# AutoFeatherDoubler.net
KiCad netlist of a schematic drawn in EAGLE
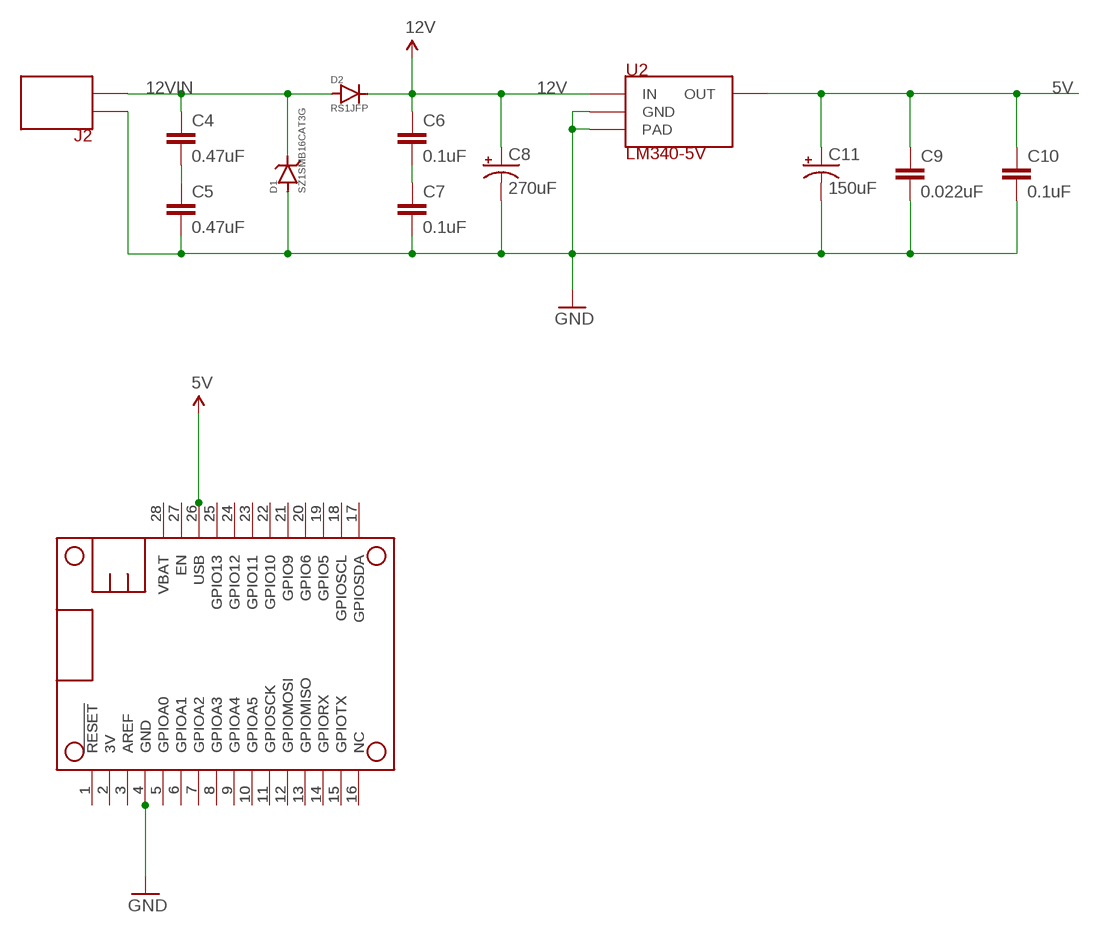
[diagram p0: schematic, sheet 1]

(export (version "E")
  (design (tool "Eeschema 10.0.6"))
  (components
    (comp (ref "C4")
      (value "0.47uF")
      (footprint "eagle-import:0805")
      (libsource (lib "eagle-import") (part "CAP-0.47UF-0805"))
    )
    (comp (ref "C5")
      (value "0.47uF")
      (footprint "eagle-import:0805")
      (libsource (lib "eagle-import") (part "CAP-0.47UF-0805"))
    )
    (comp (ref "C6")
      (value "0.1uF")
      (footprint "eagle-import:0603-CAP")
      (libsource (lib "eagle-import") (part "CAP-0.1UF-0603"))
    )
    (comp (ref "C7")
      (value "0.1uF")
      (footprint "eagle-import:0603-CAP")
      (libsource (lib "eagle-import") (part "CAP-0.1UF-0603"))
    )
    (comp (ref "C8")
      (value "270uF")
      (footprint "eagle-import:CAP-270UF-25V-RADIAL-PTH")
      (libsource (lib "eagle-import") (part "CAP-270UF-25V-RADIAL-PTH"))
    )
    (comp (ref "C9")
      (value "0.022uF")
      (footprint "eagle-import:0603-CAP")
      (libsource (lib "eagle-import") (part "CAP-0.022UF-0603"))
    )
    (comp (ref "C10")
      (value "0.1uF")
      (footprint "eagle-import:0603-CAP")
      (libsource (lib "eagle-import") (part "CAP-0.1UF-0603"))
    )
    (comp (ref "C11")
      (value "150uF")
      (footprint "eagle-import:CAP-150UF-25V-RADIAL-PTH")
      (libsource (lib "eagle-import") (part "CAP-150UF-25V-RADIAL-PTH"))
    )
    (comp (ref "D1")
      (value "SZ1SMB16CAT3G")
      (footprint "eagle-import:SZ1SMB")
      (libsource (lib "eagle-import") (part "DIODE-TVS-SZ1SMB"))
    )
    (comp (ref "D2")
      (value "RS1JFP")
      (footprint "eagle-import:SOD-123HE-ON")
      (libsource (lib "eagle-import") (part "DIODE-RS1JFP"))
    )
    (comp (ref "J2")
      (value "TERMBLOCK-2X3.5MM")
      (footprint "eagle-import:TERMBLOCK-2X3.5MM")
      (libsource (lib "eagle-import") (part "TERMBLOCK-2X3.5MM"))
    )
    (comp (ref "MS1")
      (value "FEATHERWING_NODIM")
      (footprint "eagle-import:FEATHERWING_DIM")
      (libsource (lib "eagle-import") (part "FEATHERWING_NODIM"))
    )
    (comp (ref "MS2")
      (value "FEATHERWING_NODIM")
      (footprint "eagle-import:FEATHERWING_DIM")
      (libsource (lib "eagle-import") (part "FEATHERWING_NODIM"))
    )
    (comp (ref "U2")
      (value "LM340-5V")
      (footprint "eagle-import:TO-263-3-TI")
      (libsource (lib "eagle-import") (part "LM340"))
    )
  )
  (nets
    (net (code "1") (name "/12VIN") (class "Default")
      (node (ref "C4") (pin "1") (pinfunction "1_1") (pintype "passive"))
      (node (ref "D1") (pin "C") (pinfunction "CATHODE_C") (pintype "bidirectional"))
      (node (ref "D2") (pin "2") (pinfunction "ANODE_2") (pintype "bidirectional"))
      (node (ref "J2") (pin "2") (pinfunction "2_2") (pintype "passive"))
    )
    (net (code "2") (name "5V") (class "Default")
      (node (ref "C10") (pin "1") (pinfunction "1_1") (pintype "passive"))
      (node (ref "C11") (pin "+") (pinfunction "+_+") (pintype "passive"))
      (node (ref "C9") (pin "1") (pinfunction "1_1") (pintype "passive"))
      (node (ref "MS1") (pin "26") (pinfunction "USB_26") (pintype "power_in"))
      (node (ref "MS2") (pin "26") (pinfunction "USB_26") (pintype "power_in"))
      (node (ref "U2") (pin "3") (pinfunction "OUT_3") (pintype "power_in"))
    )
    (net (code "3") (name "12V") (class "Default")
      (node (ref "C6") (pin "1") (pinfunction "1_1") (pintype "passive"))
      (node (ref "C8") (pin "+") (pinfunction "+_+") (pintype "passive"))
      (node (ref "D2") (pin "1") (pinfunction "CATHODE_1") (pintype "bidirectional"))
      (node (ref "U2") (pin "1") (pinfunction "IN_1") (pintype "power_in"))
    )
    (net (code "4") (name "GND") (class "Default")
      (node (ref "C10") (pin "2") (pinfunction "2_2") (pintype "passive"))
      (node (ref "C11") (pin "-") (pinfunction "-_-") (pintype "passive"))
      (node (ref "C5") (pin "2") (pinfunction "2_2") (pintype "passive"))
      (node (ref "C7") (pin "2") (pinfunction "2_2") (pintype "passive"))
      (node (ref "C8") (pin "-") (pinfunction "-_-") (pintype "passive"))
      (node (ref "C9") (pin "2") (pinfunction "2_2") (pintype "passive"))
      (node (ref "D1") (pin "A") (pinfunction "ANODE_A") (pintype "bidirectional"))
      (node (ref "J2") (pin "1") (pinfunction "1_1") (pintype "passive"))
      (node (ref "MS1") (pin "4") (pinfunction "GND_4") (pintype "power_in"))
      (node (ref "MS2") (pin "4") (pinfunction "GND_4") (pintype "power_in"))
      (node (ref "U2") (pin "2") (pinfunction "GND_2") (pintype "power_in"))
      (node (ref "U2") (pin "PAD") (pinfunction "PAD_PAD") (pintype "power_in"))
    )
    (net (code "5") (name "Net-(C4-Pad2)") (class "Default")
      (node (ref "C4") (pin "2") (pinfunction "2_2") (pintype "passive"))
      (node (ref "C5") (pin "1") (pinfunction "1_1") (pintype "passive"))
    )
    (net (code "6") (name "Net-(C6-Pad2)") (class "Default")
      (node (ref "C6") (pin "2") (pinfunction "2_2") (pintype "passive"))
      (node (ref "C7") (pin "1") (pinfunction "1_1") (pintype "passive"))
    )
    (net (code "7") (name "Net-(MS1-3V)") (class "Default")
      (node (ref "MS1") (pin "2") (pinfunction "3V_2") (pintype "power_in"))
      (node (ref "MS2") (pin "2") (pinfunction "3V_2") (pintype "power_in"))
    )
    (net (code "8") (name "Net-(MS1-AREF)") (class "Default")
      (node (ref "MS1") (pin "3") (pinfunction "AREF_3") (pintype "passive"))
      (node (ref "MS2") (pin "3") (pinfunction "AREF_3") (pintype "passive"))
    )
    (net (code "9") (name "Net-(MS1-EN)") (class "Default")
      (node (ref "MS1") (pin "27") (pinfunction "EN_27") (pintype "passive"))
      (node (ref "MS2") (pin "27") (pinfunction "EN_27") (pintype "passive"))
    )
    (net (code "10") (name "Net-(MS1-GPIO5)") (class "Default")
      (node (ref "MS1") (pin "19") (pinfunction "GPIO5_19") (pintype "bidirectional"))
      (node (ref "MS2") (pin "19") (pinfunction "GPIO5_19") (pintype "bidirectional"))
    )
    (net (code "11") (name "Net-(MS1-GPIO6)") (class "Default")
      (node (ref "MS1") (pin "20") (pinfunction "GPIO6_20") (pintype "bidirectional"))
      (node (ref "MS2") (pin "20") (pinfunction "GPIO6_20") (pintype "bidirectional"))
    )
    (net (code "12") (name "Net-(MS1-GPIO9)") (class "Default")
      (node (ref "MS1") (pin "21") (pinfunction "GPIO9_21") (pintype "bidirectional"))
      (node (ref "MS2") (pin "21") (pinfunction "GPIO9_21") (pintype "bidirectional"))
    )
    (net (code "13") (name "Net-(MS1-GPIO10)") (class "Default")
      (node (ref "MS1") (pin "22") (pinfunction "GPIO10_22") (pintype "bidirectional"))
      (node (ref "MS2") (pin "22") (pinfunction "GPIO10_22") (pintype "bidirectional"))
    )
    (net (code "14") (name "Net-(MS1-GPIO11)") (class "Default")
      (node (ref "MS1") (pin "23") (pinfunction "GPIO11_23") (pintype "bidirectional"))
      (node (ref "MS2") (pin "23") (pinfunction "GPIO11_23") (pintype "bidirectional"))
    )
    (net (code "15") (name "Net-(MS1-GPIO12)") (class "Default")
      (node (ref "MS1") (pin "24") (pinfunction "GPIO12_24") (pintype "bidirectional"))
      (node (ref "MS2") (pin "24") (pinfunction "GPIO12_24") (pintype "bidirectional"))
    )
    (net (code "16") (name "Net-(MS1-GPIO13)") (class "Default")
      (node (ref "MS1") (pin "25") (pinfunction "GPIO13_25") (pintype "bidirectional"))
      (node (ref "MS2") (pin "25") (pinfunction "GPIO13_25") (pintype "bidirectional"))
    )
    (net (code "17") (name "Net-(MS1-GPIOA0)") (class "Default")
      (node (ref "MS1") (pin "5") (pinfunction "GPIOA0_5") (pintype "bidirectional"))
      (node (ref "MS2") (pin "5") (pinfunction "GPIOA0_5") (pintype "bidirectional"))
    )
    (net (code "18") (name "Net-(MS1-GPIOA1)") (class "Default")
      (node (ref "MS1") (pin "6") (pinfunction "GPIOA1_6") (pintype "bidirectional"))
      (node (ref "MS2") (pin "6") (pinfunction "GPIOA1_6") (pintype "bidirectional"))
    )
    (net (code "19") (name "Net-(MS1-GPIOA2)") (class "Default")
      (node (ref "MS1") (pin "7") (pinfunction "GPIOA2_7") (pintype "bidirectional"))
      (node (ref "MS2") (pin "7") (pinfunction "GPIOA2_7") (pintype "bidirectional"))
    )
    (net (code "20") (name "Net-(MS1-GPIOA3)") (class "Default")
      (node (ref "MS1") (pin "8") (pinfunction "GPIOA3_8") (pintype "bidirectional"))
      (node (ref "MS2") (pin "8") (pinfunction "GPIOA3_8") (pintype "bidirectional"))
    )
    (net (code "21") (name "Net-(MS1-GPIOA4)") (class "Default")
      (node (ref "MS1") (pin "9") (pinfunction "GPIOA4_9") (pintype "bidirectional"))
      (node (ref "MS2") (pin "9") (pinfunction "GPIOA4_9") (pintype "bidirectional"))
    )
    (net (code "22") (name "Net-(MS1-GPIOA5)") (class "Default")
      (node (ref "MS1") (pin "10") (pinfunction "GPIOA5_10") (pintype "bidirectional"))
      (node (ref "MS2") (pin "10") (pinfunction "GPIOA5_10") (pintype "bidirectional"))
    )
    (net (code "23") (name "Net-(MS1-GPIOMISO)") (class "Default")
      (node (ref "MS1") (pin "13") (pinfunction "GPIOMISO_13") (pintype "bidirectional"))
      (node (ref "MS2") (pin "13") (pinfunction "GPIOMISO_13") (pintype "bidirectional"))
    )
    (net (code "24") (name "Net-(MS1-GPIOMOSI)") (class "Default")
      (node (ref "MS1") (pin "12") (pinfunction "GPIOMOSI_12") (pintype "bidirectional"))
      (node (ref "MS2") (pin "12") (pinfunction "GPIOMOSI_12") (pintype "bidirectional"))
    )
    (net (code "25") (name "Net-(MS1-GPIORX)") (class "Default")
      (node (ref "MS1") (pin "14") (pinfunction "GPIORX_14") (pintype "bidirectional"))
      (node (ref "MS2") (pin "14") (pinfunction "GPIORX_14") (pintype "bidirectional"))
    )
    (net (code "26") (name "Net-(MS1-GPIOSCK)") (class "Default")
      (node (ref "MS1") (pin "11") (pinfunction "GPIOSCK_11") (pintype "bidirectional"))
      (node (ref "MS2") (pin "11") (pinfunction "GPIOSCK_11") (pintype "bidirectional"))
    )
    (net (code "27") (name "Net-(MS1-GPIOSCL)") (class "Default")
      (node (ref "MS1") (pin "18") (pinfunction "GPIOSCL_18") (pintype "bidirectional"))
      (node (ref "MS2") (pin "18") (pinfunction "GPIOSCL_18") (pintype "bidirectional"))
    )
    (net (code "28") (name "Net-(MS1-GPIOSDA)") (class "Default")
      (node (ref "MS1") (pin "17") (pinfunction "GPIOSDA_17") (pintype "bidirectional"))
      (node (ref "MS2") (pin "17") (pinfunction "GPIOSDA_17") (pintype "bidirectional"))
    )
    (net (code "29") (name "Net-(MS1-GPIOTX)") (class "Default")
      (node (ref "MS1") (pin "15") (pinfunction "GPIOTX_15") (pintype "bidirectional"))
      (node (ref "MS2") (pin "15") (pinfunction "GPIOTX_15") (pintype "bidirectional"))
    )
    (net (code "30") (name "Net-(MS1-NC)") (class "Default")
      (node (ref "MS1") (pin "16") (pinfunction "NC_16") (pintype "passive"))
      (node (ref "MS2") (pin "16") (pinfunction "NC_16") (pintype "passive"))
    )
    (net (code "31") (name "Net-(MS1-VBAT)") (class "Default")
      (node (ref "MS1") (pin "28") (pinfunction "VBAT_28") (pintype "power_in"))
      (node (ref "MS2") (pin "28") (pinfunction "VBAT_28") (pintype "power_in"))
    )
    (net (code "32") (name "Net-(MS1-~{RESET})") (class "Default")
      (node (ref "MS1") (pin "1") (pinfunction "~{RESET}_1") (pintype "input"))
      (node (ref "MS2") (pin "1") (pinfunction "~{RESET}_1") (pintype "input"))
    )
  )
)
